# power_dist.net
KiCad netlist of a schematic drawn in EAGLE
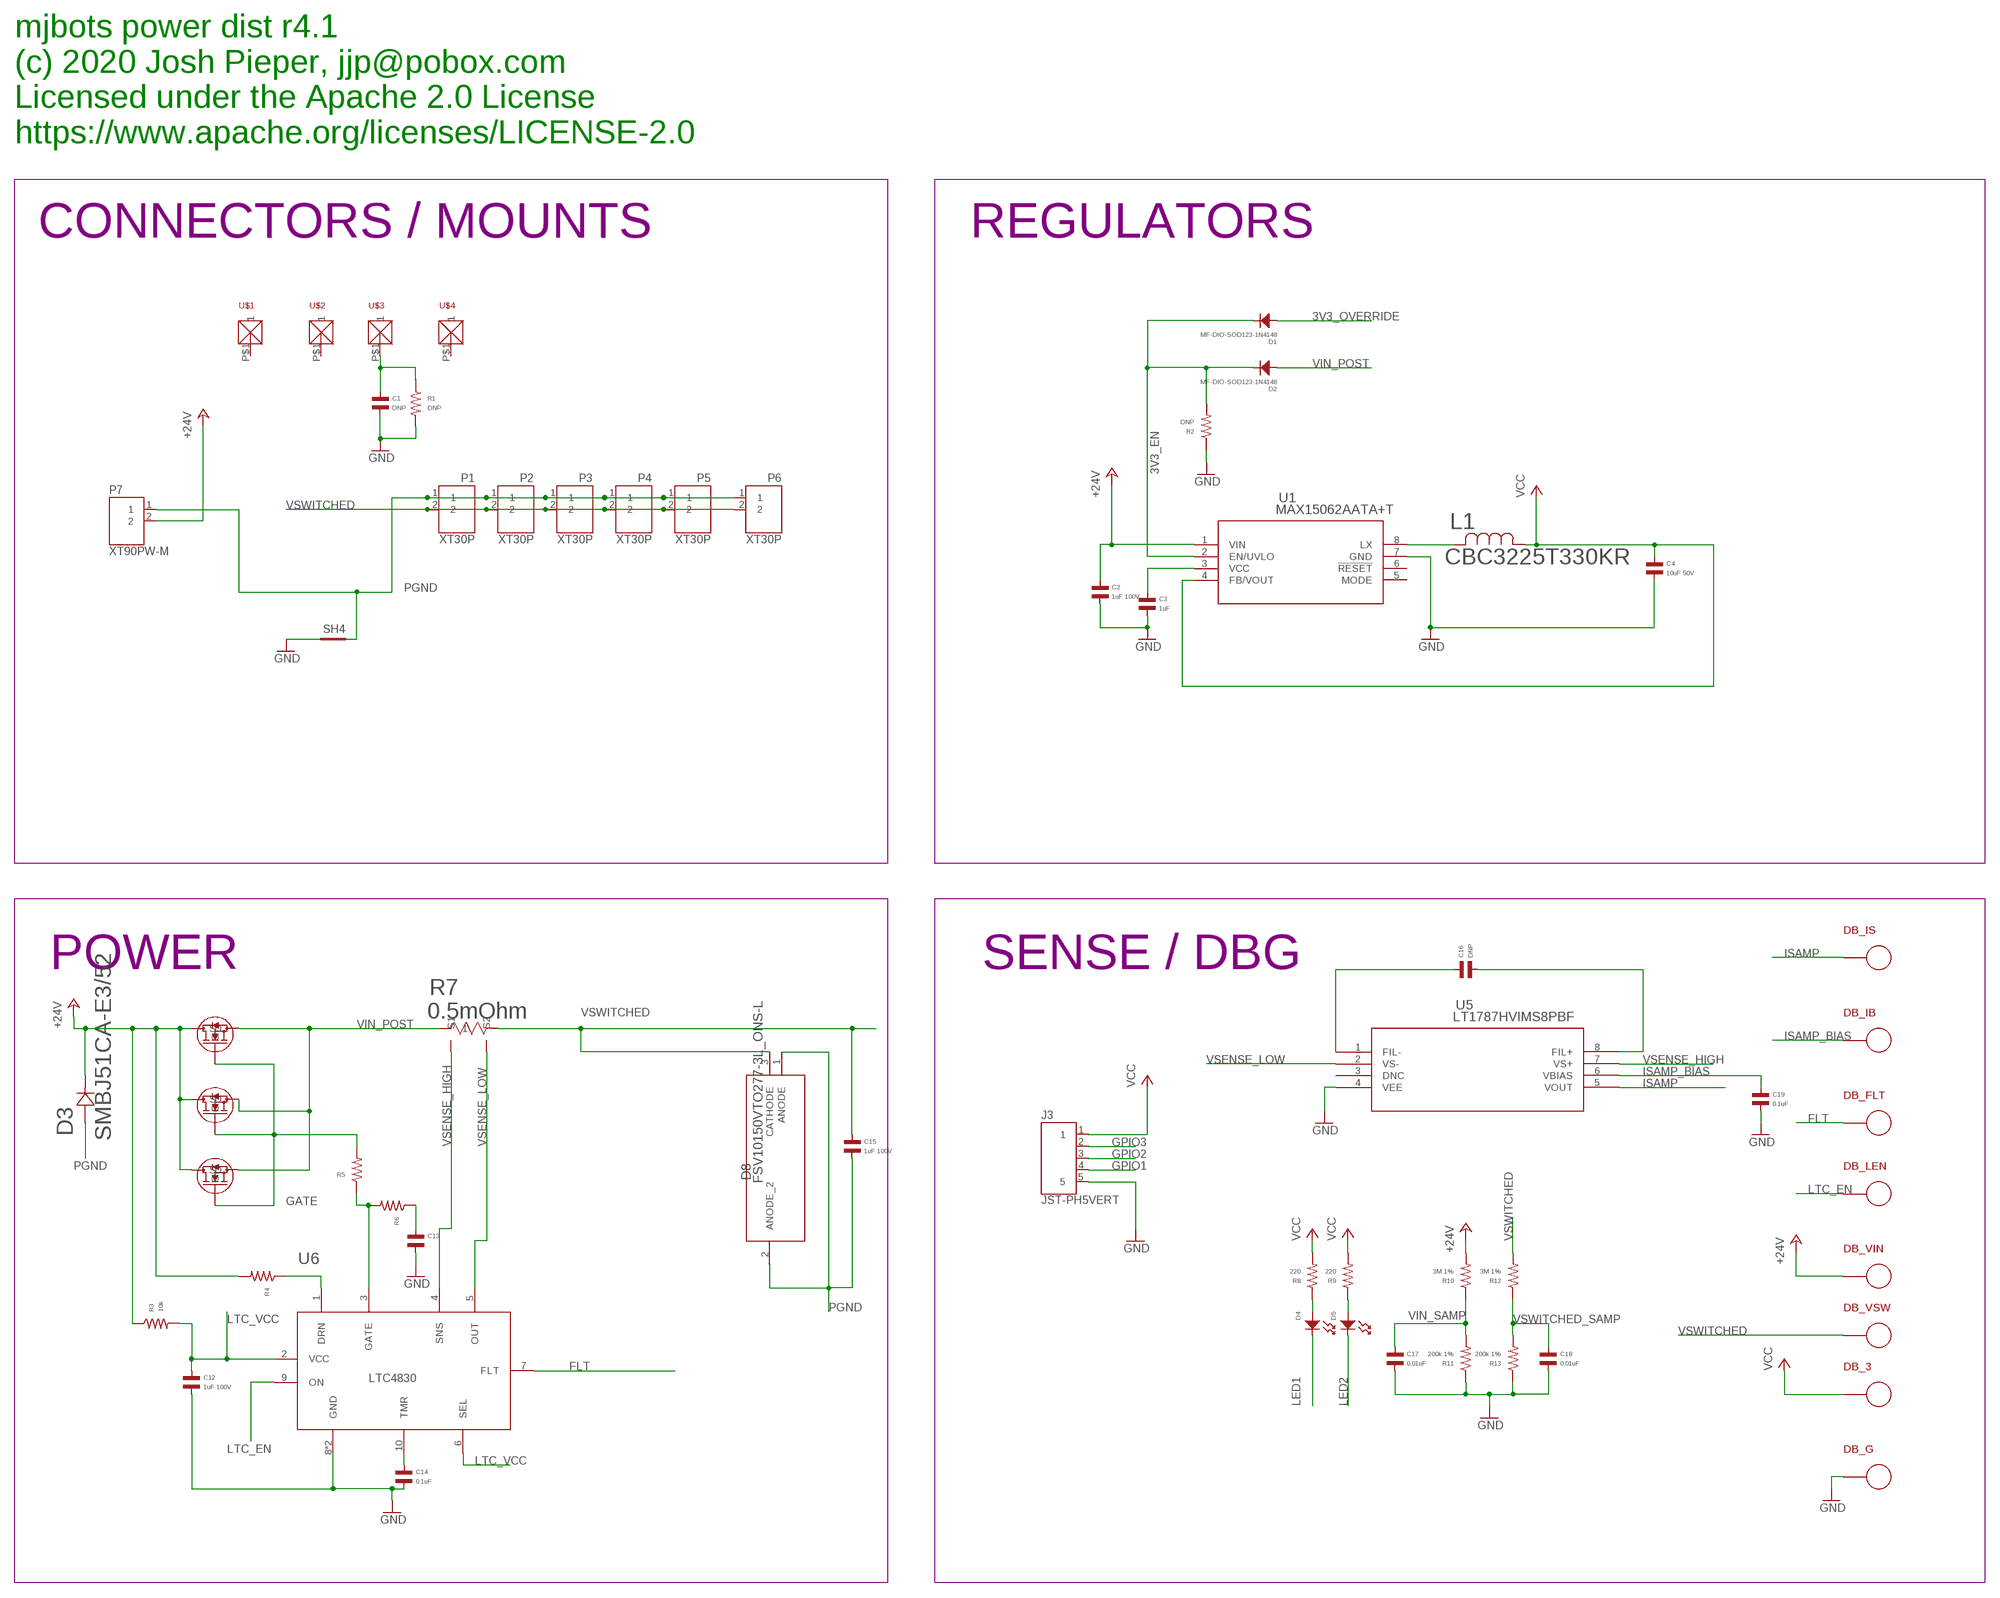
[diagram p0: schematic, sheet 1, part 1 of 2]
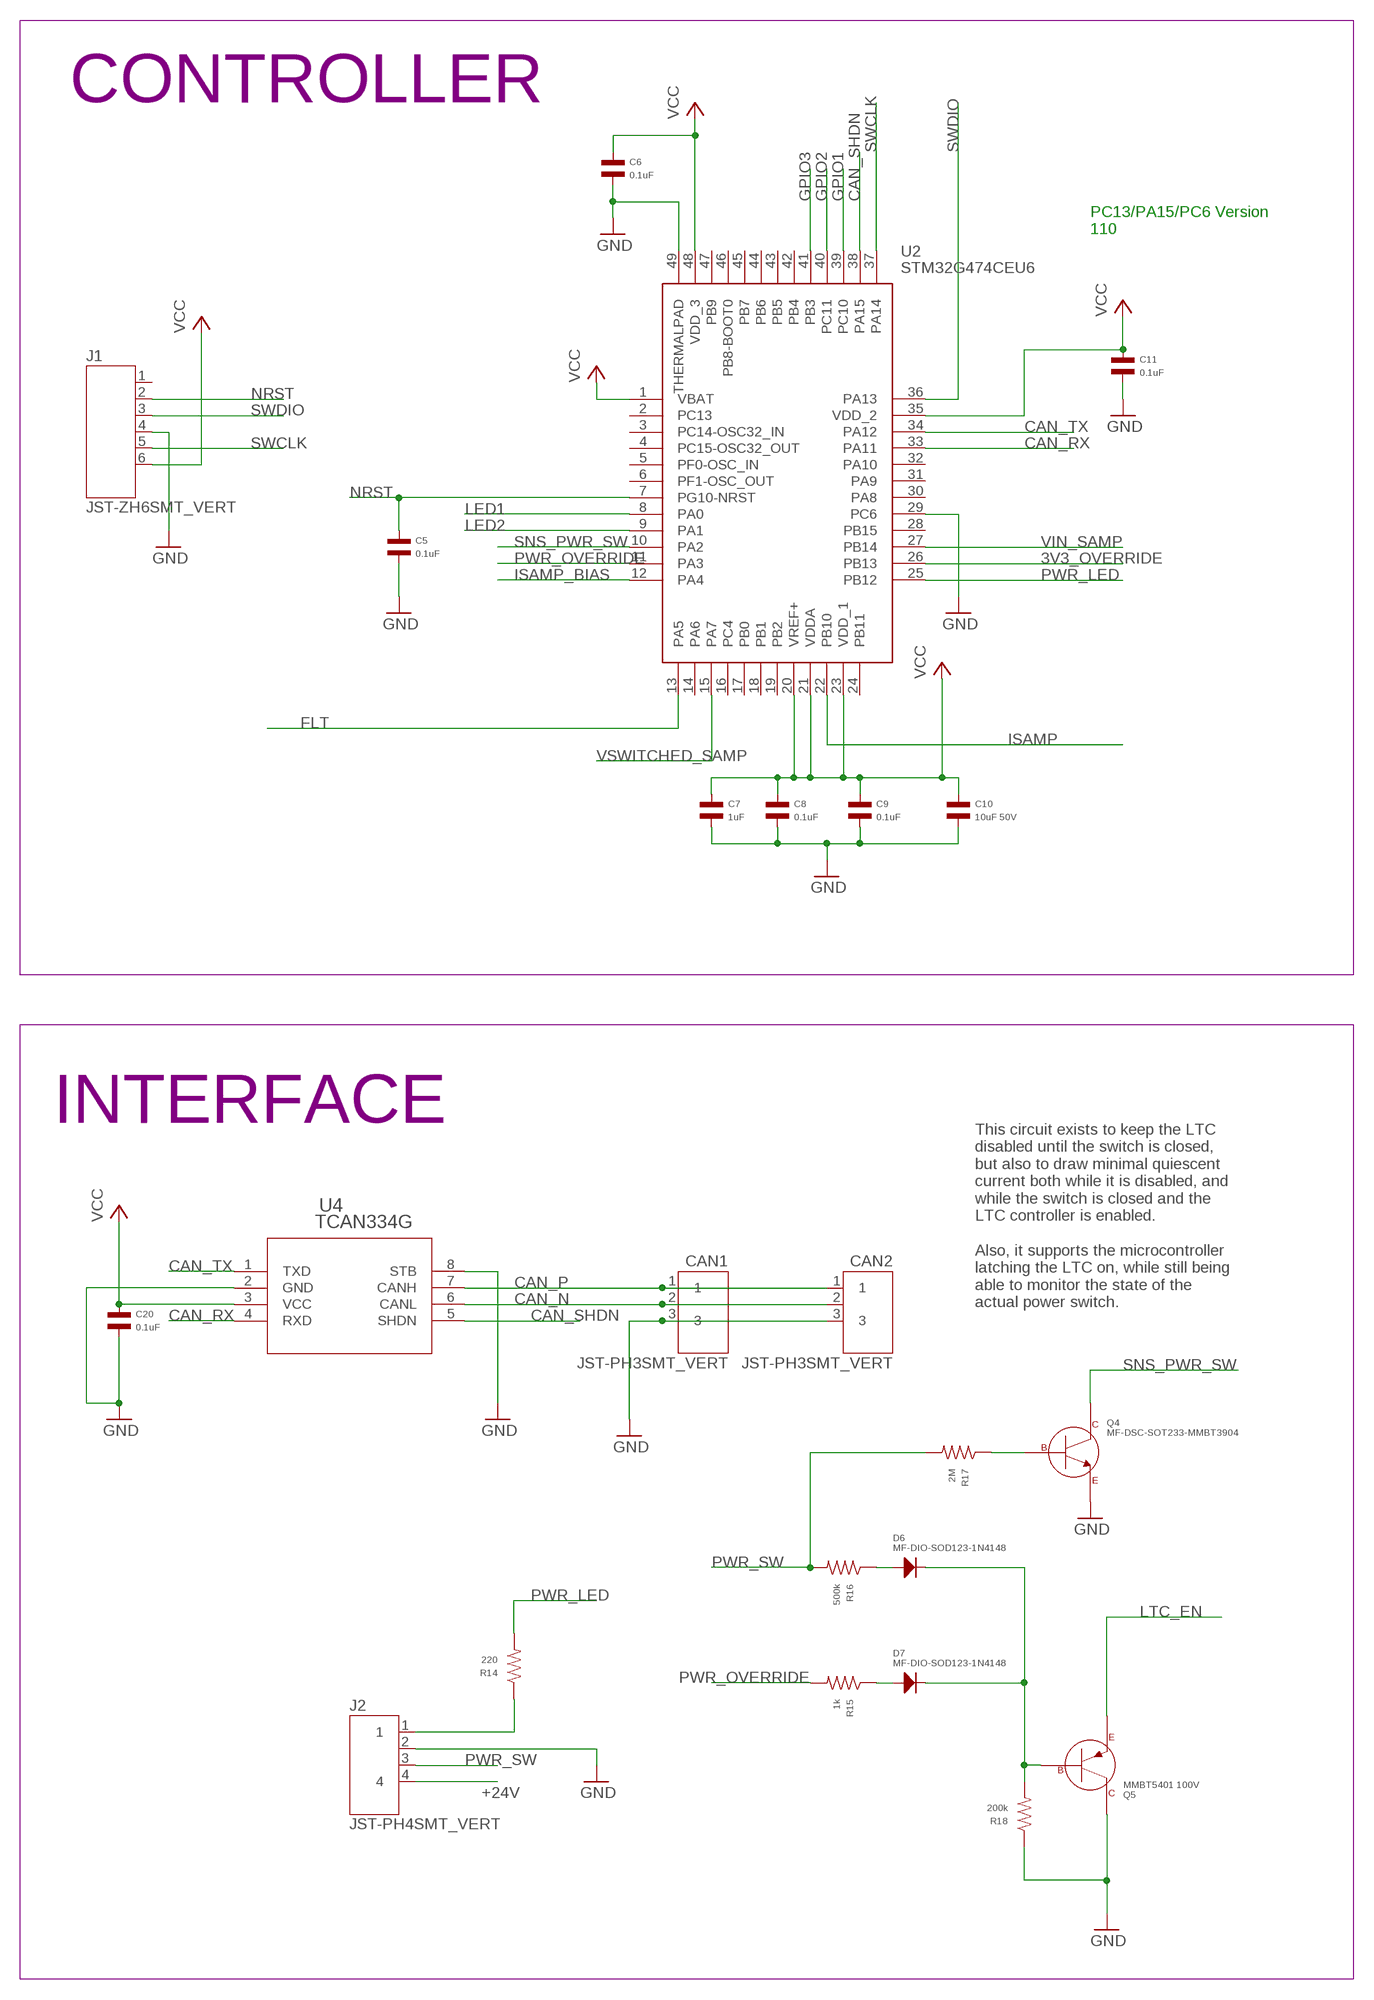
[diagram p1: schematic, sheet 1, part 2 of 2]

(export (version "E")
  (design (tool "Eeschema 10.0.6"))
  (components
    (comp (ref "C1")
      (value "DNP")
      (footprint "eagle-import:C0603")
      (fields (field (name "POPULATE") "0"))
      (libsource (lib "eagle-import") (part "CAPACITOR_NP_0603"))
    )
    (comp (ref "C2")
      (value "1uF 100V")
      (footprint "eagle-import:C0805")
      (fields (field (name "MF") "MURATA") (field (name "MPN") "GCM21BC72A105KE36L"))
      (libsource (lib "eagle-import") (part "CAPACITOR_NP_0805"))
    )
    (comp (ref "C3")
      (value "1uF")
      (footprint "eagle-import:C0603")
      (fields (field (name "HOUSEPART") "1") (field (name "MPN") "MF-CAP-0603-1uF"))
      (libsource (lib "eagle-import") (part "CAPACITOR_NP_0603"))
    )
    (comp (ref "C4")
      (value "10uF 50V")
      (footprint "eagle-import:C1206")
      (fields (field (name "MF") "TDK") (field (name "MPN") "C3216X7R1H106K160AE"))
      (libsource (lib "eagle-import") (part "CAPACITOR_NP_1206"))
    )
    (comp (ref "C5")
      (value "0.1uF")
      (footprint "eagle-import:C0603")
      (fields (field (name "HOUSEPART") "1") (field (name "MPN") "MF-CAP-0603-0.1uF"))
      (libsource (lib "eagle-import") (part "CAPACITOR_NP_0603"))
    )
    (comp (ref "C6")
      (value "0.1uF")
      (footprint "eagle-import:C0603")
      (fields (field (name "HOUSEPART") "1") (field (name "MPN") "MF-CAP-0603-0.1uF"))
      (libsource (lib "eagle-import") (part "CAPACITOR_NP_0603"))
    )
    (comp (ref "C7")
      (value "1uF")
      (footprint "eagle-import:C0603")
      (fields (field (name "HOUSEPART") "1") (field (name "MPN") "MF-CAP-0603-1uF"))
      (libsource (lib "eagle-import") (part "CAPACITOR_NP_0603"))
    )
    (comp (ref "C8")
      (value "0.1uF")
      (footprint "eagle-import:C0603")
      (fields (field (name "HOUSEPART") "1") (field (name "MPN") "MF-CAP-0603-0.1uF"))
      (libsource (lib "eagle-import") (part "CAPACITOR_NP_0603"))
    )
    (comp (ref "C9")
      (value "0.1uF")
      (footprint "eagle-import:C0603")
      (fields (field (name "HOUSEPART") "1") (field (name "MPN") "MF-CAP-0603-0.1uF"))
      (libsource (lib "eagle-import") (part "CAPACITOR_NP_0603"))
    )
    (comp (ref "C10")
      (value "10uF 50V")
      (footprint "eagle-import:C1206")
      (fields (field (name "MF") "TDK") (field (name "MPN") "C3216X7R1H106K160AE"))
      (libsource (lib "eagle-import") (part "CAPACITOR_NP_1206"))
    )
    (comp (ref "C11")
      (value "0.1uF")
      (footprint "eagle-import:C0603")
      (fields (field (name "HOUSEPART") "1") (field (name "MPN") "MF-CAP-0603-0.1uF"))
      (libsource (lib "eagle-import") (part "CAPACITOR_NP_0603"))
    )
    (comp (ref "C12")
      (value "1uF 100V")
      (footprint "eagle-import:C0805")
      (fields (field (name "MF") "MURATA") (field (name "MPN") "GCM21BC72A105KE36L"))
      (libsource (lib "eagle-import") (part "CAPACITOR_NP_0805"))
    )
    (comp (ref "C13")
      (value "CAPACITOR_NP_0603")
      (footprint "eagle-import:C0603")
      (fields (field (name "HOUSEPART") "1"))
      (libsource (lib "eagle-import") (part "CAPACITOR_NP_0603"))
    )
    (comp (ref "C14")
      (value "0.1uF")
      (footprint "eagle-import:C0603")
      (fields (field (name "HOUSEPART") "1") (field (name "MPN") "MF-CAP-0603-0.1uF"))
      (libsource (lib "eagle-import") (part "CAPACITOR_NP_0603"))
    )
    (comp (ref "C15")
      (value "1uF 100V")
      (footprint "eagle-import:C0805")
      (fields (field (name "MF") "MURATA") (field (name "MPN") "GCM21BC72A105KE36L"))
      (libsource (lib "eagle-import") (part "CAPACITOR_NP_0805"))
    )
    (comp (ref "C16")
      (value "DNP")
      (footprint "eagle-import:C0603")
      (fields (field (name "POPULATE") "0"))
      (libsource (lib "eagle-import") (part "CAPACITOR_NP_0603"))
    )
    (comp (ref "C17")
      (value "0.01uF")
      (footprint "eagle-import:C0603")
      (fields (field (name "HOUSEPART") "1") (field (name "MPN") "MF-CAP-0603-0.01uF"))
      (libsource (lib "eagle-import") (part "CAPACITOR_NP_0603"))
    )
    (comp (ref "C18")
      (value "0.01uF")
      (footprint "eagle-import:C0603")
      (fields (field (name "HOUSEPART") "1") (field (name "MPN") "MF-CAP-0603-0.01uF"))
      (libsource (lib "eagle-import") (part "CAPACITOR_NP_0603"))
    )
    (comp (ref "C19")
      (value "0.1uF")
      (footprint "eagle-import:C0603")
      (fields (field (name "HOUSEPART") "1") (field (name "MPN") "MF-CAP-0603-0.1uF"))
      (libsource (lib "eagle-import") (part "CAPACITOR_NP_0603"))
    )
    (comp (ref "C20")
      (value "0.1uF")
      (footprint "eagle-import:C0603")
      (fields (field (name "HOUSEPART") "1") (field (name "MPN") "MF-CAP-0603-0.1uF"))
      (libsource (lib "eagle-import") (part "CAPACITOR_NP_0603"))
    )
    (comp (ref "CAN1")
      (value "JST-PH3SMT_VERT")
      (footprint "eagle-import:JST_B3B_PH-SM4-TB(LF)(SN)")
      (fields (field (name "MF") "JST") (field (name "MPN") "B3B-PH-SM4-TB(LF)(SN)"))
      (libsource (lib "eagle-import") (part "JST-PH3SMT_VERT"))
    )
    (comp (ref "CAN2")
      (value "JST-PH3SMT_VERT")
      (footprint "eagle-import:JST_B3B_PH-SM4-TB(LF)(SN)")
      (fields (field (name "MF") "JST") (field (name "MPN") "B3B-PH-SM4-TB(LF)(SN)"))
      (libsource (lib "eagle-import") (part "JST-PH3SMT_VERT"))
    )
    (comp (ref "D1")
      (value "MF-DIO-SOD123-1N4148")
      (footprint "eagle-import:SOD-123")
      (fields (field (name "HOUSEPART") "YES"))
      (libsource (lib "eagle-import") (part "DIODES_SOD-123_1N4148"))
    )
    (comp (ref "D2")
      (value "MF-DIO-SOD123-1N4148")
      (footprint "eagle-import:SOD-123")
      (fields (field (name "HOUSEPART") "YES"))
      (libsource (lib "eagle-import") (part "DIODES_SOD-123_1N4148"))
    )
    (comp (ref "D3")
      (value "SMBJ51CA-E3/52")
      (footprint "eagle-import:DIODE_DO-214AC")
      (libsource (lib "eagle-import") (part "SMBJ51CA-E3/52"))
    )
    (comp (ref "D4")
      (value "LED_SINGLE-0603")
      (footprint "eagle-import:LED0603")
      (fields
        (field (name "HOUSEPART") "NO")
        (field (name "HOUSEPART_1") "1")
        (field (name "MPN") "MF-LED-0603-RED")
      )
      (libsource (lib "eagle-import") (part "LED_SINGLE-0603"))
    )
    (comp (ref "D5")
      (value "LED_SINGLE-0603")
      (footprint "eagle-import:LED0603")
      (fields
        (field (name "HOUSEPART") "NO")
        (field (name "HOUSEPART_1") "1")
        (field (name "MPN") "MF-LED-0603-RED")
      )
      (libsource (lib "eagle-import") (part "LED_SINGLE-0603"))
    )
    (comp (ref "D6")
      (value "MF-DIO-SOD123-1N4148")
      (footprint "eagle-import:SOD-123")
      (fields (field (name "HOUSEPART") "YES"))
      (libsource (lib "eagle-import") (part "DIODES_SOD-123_1N4148"))
    )
    (comp (ref "D7")
      (value "MF-DIO-SOD123-1N4148")
      (footprint "eagle-import:SOD-123")
      (fields (field (name "HOUSEPART") "YES"))
      (libsource (lib "eagle-import") (part "DIODES_SOD-123_1N4148"))
    )
    (comp (ref "D8")
      (value "FSV10150VTO277-3L_ONS-L")
      (footprint "eagle-import:TO277-3L_ONS-L")
      (fields
        (field (name "MANUFACTURER_PART_NUMBER") "FSV10150V")
        (field (name "COPYRIGHT") "Copyright (C) 2018 Accelerated Designs. All rights reserved")
      )
      (libsource (lib "eagle-import") (part "FSV10150VTO277-3L_ONS-L"))
    )
    (comp (ref "DB_3")
      (value "PAD24AWG_PAD")
      (footprint "eagle-import:24AWG_PAD")
      (libsource (lib "eagle-import") (part "PAD24AWG_PAD"))
    )
    (comp (ref "DB_FLT")
      (value "PAD24AWG_PAD")
      (footprint "eagle-import:24AWG_PAD")
      (libsource (lib "eagle-import") (part "PAD24AWG_PAD"))
    )
    (comp (ref "DB_G")
      (value "PAD24AWG_PAD")
      (footprint "eagle-import:24AWG_PAD")
      (libsource (lib "eagle-import") (part "PAD24AWG_PAD"))
    )
    (comp (ref "DB_IB")
      (value "PAD24AWG_PAD")
      (footprint "eagle-import:24AWG_PAD")
      (libsource (lib "eagle-import") (part "PAD24AWG_PAD"))
    )
    (comp (ref "DB_IS")
      (value "PAD24AWG_PAD")
      (footprint "eagle-import:24AWG_PAD")
      (libsource (lib "eagle-import") (part "PAD24AWG_PAD"))
    )
    (comp (ref "DB_LEN")
      (value "PAD24AWG_PAD")
      (footprint "eagle-import:24AWG_PAD")
      (libsource (lib "eagle-import") (part "PAD24AWG_PAD"))
    )
    (comp (ref "DB_VIN")
      (value "PAD24AWG_PAD")
      (footprint "eagle-import:24AWG_PAD")
      (libsource (lib "eagle-import") (part "PAD24AWG_PAD"))
    )
    (comp (ref "DB_VSW")
      (value "PAD24AWG_PAD")
      (footprint "eagle-import:24AWG_PAD")
      (libsource (lib "eagle-import") (part "PAD24AWG_PAD"))
    )
    (comp (ref "J1")
      (value "JST-ZH6SMT_VERT")
      (footprint "eagle-import:JST_B6B-ZR-SM4-TF(LF)(SN)")
      (fields (field (name "MF") "JST") (field (name "MPN") "B6B-ZR-SM4-TF(LF)(SN)"))
      (libsource (lib "eagle-import") (part "JST-ZH6SMT_VERT"))
    )
    (comp (ref "J2")
      (value "JST-PH4SMT_VERT")
      (footprint "eagle-import:JST_B4B_PH-SM4-TB(LF)(SN)")
      (fields (field (name "MF") "JST") (field (name "MPN") "B4B-PH-SM4-TB(LF)(SN)"))
      (libsource (lib "eagle-import") (part "JST-PH4SMT_VERT"))
    )
    (comp (ref "J3")
      (value "JST-PH5VERT")
      (footprint "eagle-import:JST_B5B_PH-SM4-TB(LF)(SN)")
      (fields (field (name "MF") "JST") (field (name "MPN") "B5B-PH-SM4-TB(LF)(SN)"))
      (libsource (lib "eagle-import") (part "JST-PH5VERT"))
    )
    (comp (ref "L1")
      (value "CBC3225T330KR")
      (footprint "eagle-import:IND_TAIYO_CBC3225_TAY")
      (libsource (lib "eagle-import") (part "CBC3225T330KR"))
    )
    (comp (ref "P1")
      (value "XT30P")
      (footprint "eagle-import:XT30P")
      (fields (field (name "MF") "AMASS") (field (name "MPN") "XT30UPB-F"))
      (libsource (lib "eagle-import") (part "XT30P"))
    )
    (comp (ref "P2")
      (value "XT30P")
      (footprint "eagle-import:XT30P")
      (fields (field (name "MF") "AMASS") (field (name "MPN") "XT30UPB-F"))
      (libsource (lib "eagle-import") (part "XT30P"))
    )
    (comp (ref "P3")
      (value "XT30P")
      (footprint "eagle-import:XT30P")
      (fields (field (name "MF") "AMASS") (field (name "MPN") "XT30UPB-F"))
      (libsource (lib "eagle-import") (part "XT30P"))
    )
    (comp (ref "P4")
      (value "XT30P")
      (footprint "eagle-import:XT30P")
      (fields (field (name "MF") "AMASS") (field (name "MPN") "XT30UPB-F"))
      (libsource (lib "eagle-import") (part "XT30P"))
    )
    (comp (ref "P5")
      (value "XT30P")
      (footprint "eagle-import:XT30P")
      (fields (field (name "MF") "AMASS") (field (name "MPN") "XT30UPB-F"))
      (libsource (lib "eagle-import") (part "XT30P"))
    )
    (comp (ref "P6")
      (value "XT30P")
      (footprint "eagle-import:XT30P")
      (fields (field (name "MF") "AMASS") (field (name "MPN") "XT30UPB-F"))
      (libsource (lib "eagle-import") (part "XT30P"))
    )
    (comp (ref "P7")
      (value "XT90PW-M")
      (footprint "eagle-import:XT90PW-M")
      (libsource (lib "eagle-import") (part "XT90PW-M"))
    )
    (comp (ref "Q1")
      (value "PSMN4R8-100BSEJ")
      (footprint "eagle-import:D2PAK_SOT404_NEX")
      (fields (field (name "COPYRIGHT") "Copyright (C) 2018 Accelerated Designs. All rights reserved"))
      (libsource (lib "eagle-import") (part "PSMN4R8-100BSEJ"))
    )
    (comp (ref "Q2")
      (value "PSMN4R8-100BSEJ")
      (footprint "eagle-import:D2PAK_SOT404_NEX")
      (fields (field (name "COPYRIGHT") "Copyright (C) 2018 Accelerated Designs. All rights reserved"))
      (libsource (lib "eagle-import") (part "PSMN4R8-100BSEJ"))
    )
    (comp (ref "Q3")
      (value "PSMN4R8-100BSEJ")
      (footprint "eagle-import:D2PAK_SOT404_NEX")
      (fields (field (name "COPYRIGHT") "Copyright (C) 2018 Accelerated Designs. All rights reserved"))
      (libsource (lib "eagle-import") (part "PSMN4R8-100BSEJ"))
    )
    (comp (ref "Q4")
      (value "MF-DSC-SOT233-MMBT3904")
      (footprint "eagle-import:SOT-23-3")
      (fields (field (name "HOUSEPART") "YES"))
      (libsource (lib "eagle-import") (part "NPN_BJT_SOT-23-3MMBT3904"))
    )
    (comp (ref "Q5")
      (value "MMBT5401 100V")
      (footprint "eagle-import:SOT-23-3")
      (fields
        (field (name "HOUSEPART") "YES")
        (field (name "MPN") "MF-DSC-SOT233-MMBT3906")
        (field (name "MF") "DIODES")
        (field (name "MPN_1") "MMBT5401-7-F")
      )
      (libsource (lib "eagle-import") (part "PNP_BJT_SOT-23-3_MMBT3906"))
    )
    (comp (ref "R1")
      (value "DNP")
      (footprint "eagle-import:R0603")
      (fields (field (name "POPULATE") "0"))
      (libsource (lib "eagle-import") (part "RESISTOR_0603"))
    )
    (comp (ref "R2")
      (value "DNP")
      (footprint "eagle-import:R0603")
      (fields (field (name "HOUSEPART") "1"))
      (libsource (lib "eagle-import") (part "RESISTOR_0603"))
    )
    (comp (ref "R3")
      (value "10k")
      (footprint "eagle-import:R0603")
      (fields (field (name "HOUSEPART") "1"))
      (libsource (lib "eagle-import") (part "RESISTOR_0603"))
    )
    (comp (ref "R4")
      (value "RESISTOR_0603")
      (footprint "eagle-import:R0603")
      (fields (field (name "HOUSEPART") "1"))
      (libsource (lib "eagle-import") (part "RESISTOR_0603"))
    )
    (comp (ref "R5")
      (value "RESISTOR_0603")
      (footprint "eagle-import:R0603")
      (fields (field (name "HOUSEPART") "1"))
      (libsource (lib "eagle-import") (part "RESISTOR_0603"))
    )
    (comp (ref "R6")
      (value "RESISTOR_0603")
      (footprint "eagle-import:R0603")
      (fields (field (name "HOUSEPART") "1"))
      (libsource (lib "eagle-import") (part "RESISTOR_0603"))
    )
    (comp (ref "R7")
      (value "0.5mOhm")
      (footprint "eagle-import:SHUNT2512")
      (fields (field (name "MF") "VISHAY DALE") (field (name "MPN") "WSLF2512L5000FEA"))
      (libsource (lib "eagle-import") (part "SENSE_RESISTOR2512"))
    )
    (comp (ref "R8")
      (value "220")
      (footprint "eagle-import:R0603")
      (fields (field (name "HOUSEPART") "1") (field (name "MPN") "MF-RES-0603-220"))
      (libsource (lib "eagle-import") (part "RESISTOR_0603"))
    )
    (comp (ref "R9")
      (value "220")
      (footprint "eagle-import:R0603")
      (fields (field (name "HOUSEPART") "1") (field (name "MPN") "MF-RES-0603-220"))
      (libsource (lib "eagle-import") (part "RESISTOR_0603"))
    )
    (comp (ref "R10")
      (value "3M 1%")
      (footprint "eagle-import:R0603")
      (fields (field (name "HOUSEPART") "1"))
      (libsource (lib "eagle-import") (part "RESISTOR_0603"))
    )
    (comp (ref "R11")
      (value "200k 1%")
      (footprint "eagle-import:R0603")
      (fields (field (name "HOUSEPART") "1"))
      (libsource (lib "eagle-import") (part "RESISTOR_0603"))
    )
    (comp (ref "R12")
      (value "3M 1%")
      (footprint "eagle-import:R0603")
      (fields (field (name "HOUSEPART") "1"))
      (libsource (lib "eagle-import") (part "RESISTOR_0603"))
    )
    (comp (ref "R13")
      (value "200k 1%")
      (footprint "eagle-import:R0603")
      (fields (field (name "HOUSEPART") "1"))
      (libsource (lib "eagle-import") (part "RESISTOR_0603"))
    )
    (comp (ref "R14")
      (value "220")
      (footprint "eagle-import:R0603")
      (fields (field (name "HOUSEPART") "1") (field (name "MPN") "MF-RES-0603-220"))
      (libsource (lib "eagle-import") (part "RESISTOR_0603"))
    )
    (comp (ref "R15")
      (value "1k")
      (footprint "eagle-import:R0603")
      (fields (field (name "HOUSEPART") "1"))
      (libsource (lib "eagle-import") (part "RESISTOR_0603"))
    )
    (comp (ref "R16")
      (value "500k")
      (footprint "eagle-import:R0603")
      (fields (field (name "HOUSEPART") "1"))
      (libsource (lib "eagle-import") (part "RESISTOR_0603"))
    )
    (comp (ref "R17")
      (value "2M")
      (footprint "eagle-import:R0603")
      (fields (field (name "HOUSEPART") "1"))
      (libsource (lib "eagle-import") (part "RESISTOR_0603"))
    )
    (comp (ref "R18")
      (value "200k")
      (footprint "eagle-import:R0603")
      (fields (field (name "HOUSEPART") "1"))
      (libsource (lib "eagle-import") (part "RESISTOR_0603"))
    )
    (comp (ref "SH4")
      (value "SHORTBIG")
      (footprint "eagle-import:SHORT_TOP-BIG")
      (libsource (lib "eagle-import") (part "SHORTBIG"))
    )
    (comp (ref "U$1")
      (value "MOUNT")
      (footprint "eagle-import:M2.5MOUNT")
      (libsource (lib "eagle-import") (part "MOUNT"))
    )
    (comp (ref "U$2")
      (value "MOUNT")
      (footprint "eagle-import:M2.5MOUNT")
      (libsource (lib "eagle-import") (part "MOUNT"))
    )
    (comp (ref "U$3")
      (value "MOUNT")
      (footprint "eagle-import:M2.5MOUNT")
      (libsource (lib "eagle-import") (part "MOUNT"))
    )
    (comp (ref "U$4")
      (value "MOUNT")
      (footprint "eagle-import:M2.5MOUNT")
      (libsource (lib "eagle-import") (part "MOUNT"))
    )
    (comp (ref "U1")
      (value "MAX15062AATA+T")
      (footprint "eagle-import:21-0487A_MXM")
      (fields (field (name "COPYRIGHT") "Copyright (C) 2018 Accelerated Designs. All rights reserved"))
      (libsource (lib "eagle-import") (part "MAX15062AATA+T"))
    )
    (comp (ref "U2")
      (value "STM32G474CEU6")
      (footprint "eagle-import:QFN50P700X700X60-49N")
      (fields (field (name "MOUSER_PART_NUMBER") "511-STM32G474CEU6") (field (name "MF") "ST"))
      (libsource (lib "eagle-import") (part "STM32G474CEU6"))
    )
    (comp (ref "U4")
      (value "TCAN334G")
      (footprint "eagle-import:SOIC8")
      (fields (field (name "MF") "TI") (field (name "MPN") "TCAN334GDR"))
      (libsource (lib "eagle-import") (part "TCAN334G"))
    )
    (comp (ref "U5")
      (value "LT1787HVIMS8PBF")
      (footprint "eagle-import:MSOP-8_MS")
      (fields
        (field (name "DIGI-KEY_PART_NUMBER") "LT1787HVIMS8#PBF-ND")
        (field (name "MF") "Linear Technology")
        (field (name "MP") "LT1787HVIMS8#PBF")
      )
      (libsource (lib "eagle-import") (part "LT1787HVIMS8PBF"))
    )
    (comp (ref "U6")
      (value "LTC4830")
      (footprint "eagle-import:DFN10")
      (libsource (lib "eagle-import") (part "LTC4830"))
    )
  )
  (nets
    (net (code "1") (name "+24V") (class "Default")
      (node (ref "C2") (pin "P$1") (pinfunction "P$1_P$1") (pintype "passive"))
      (node (ref "D3") (pin "1") (pinfunction "1_1") (pintype "passive"))
      (node (ref "DB_VIN") (pin "P$1") (pinfunction "P$1_P$1") (pintype "bidirectional"))
      (node (ref "J2") (pin "4") (pinfunction "4_4") (pintype "passive"))
      (node (ref "P7") (pin "2") (pinfunction "2_2") (pintype "passive"))
      (node (ref "Q1") (pin "2") (pinfunction "D_2") (pintype "passive"))
      (node (ref "Q2") (pin "2") (pinfunction "D_2") (pintype "passive"))
      (node (ref "Q3") (pin "2") (pinfunction "D_2") (pintype "passive"))
      (node (ref "R10") (pin "P$2") (pinfunction "P$2_P$2") (pintype "passive"))
      (node (ref "R3") (pin "P$1") (pinfunction "P$1_P$1") (pintype "passive"))
      (node (ref "R4") (pin "P$2") (pinfunction "P$2_P$2") (pintype "passive"))
      (node (ref "U1") (pin "1") (pinfunction "VIN_1") (pintype "input"))
    )
    (net (code "2") (name "/3V3_EN") (class "Default")
      (node (ref "D1") (pin "CATHODE") (pinfunction "CATHODE_CATHODE") (pintype "bidirectional"))
      (node (ref "D2") (pin "CATHODE") (pinfunction "CATHODE_CATHODE") (pintype "bidirectional"))
      (node (ref "R2") (pin "P$2") (pinfunction "P$2_P$2") (pintype "passive"))
      (node (ref "U1") (pin "2") (pinfunction "EN/UVLO_2") (pintype "input"))
    )
    (net (code "3") (name "/3V3_OVERRIDE") (class "Default")
      (node (ref "D1") (pin "ANODE") (pinfunction "ANODE_ANODE") (pintype "bidirectional"))
      (node (ref "U2") (pin "26") (pinfunction "PB13_26") (pintype "bidirectional"))
    )
    (net (code "4") (name "/CAN_N") (class "Default")
      (node (ref "CAN1") (pin "2") (pinfunction "2_2") (pintype "passive"))
      (node (ref "CAN2") (pin "2") (pinfunction "2_2") (pintype "passive"))
      (node (ref "U4") (pin "6") (pinfunction "CANL_6") (pintype "bidirectional"))
    )
    (net (code "5") (name "/CAN_P") (class "Default")
      (node (ref "CAN1") (pin "1") (pinfunction "1_1") (pintype "passive"))
      (node (ref "CAN2") (pin "1") (pinfunction "1_1") (pintype "passive"))
      (node (ref "U4") (pin "7") (pinfunction "CANH_7") (pintype "bidirectional"))
    )
    (net (code "6") (name "/CAN_RX") (class "Default")
      (node (ref "U2") (pin "33") (pinfunction "PA11_33") (pintype "bidirectional"))
      (node (ref "U4") (pin "4") (pinfunction "RXD_4") (pintype "output"))
    )
    (net (code "7") (name "/CAN_SHDN") (class "Default")
      (node (ref "U2") (pin "38") (pinfunction "PA15_38") (pintype "bidirectional"))
      (node (ref "U4") (pin "5") (pinfunction "SHDN_5") (pintype "input"))
    )
    (net (code "8") (name "/CAN_TX") (class "Default")
      (node (ref "U2") (pin "34") (pinfunction "PA12_34") (pintype "bidirectional"))
      (node (ref "U4") (pin "1") (pinfunction "TXD_1") (pintype "input"))
    )
    (net (code "9") (name "/FLT") (class "Default")
      (node (ref "DB_FLT") (pin "P$1") (pinfunction "P$1_P$1") (pintype "bidirectional"))
      (node (ref "U2") (pin "13") (pinfunction "PA5_13") (pintype "bidirectional"))
      (node (ref "U6") (pin "7") (pinfunction "FLT_7") (pintype "bidirectional"))
    )
    (net (code "10") (name "/GATE") (class "Default")
      (node (ref "Q1") (pin "1") (pinfunction "G_1") (pintype "passive"))
      (node (ref "Q2") (pin "1") (pinfunction "G_1") (pintype "passive"))
      (node (ref "Q3") (pin "1") (pinfunction "G_1") (pintype "passive"))
      (node (ref "R5") (pin "P$2") (pinfunction "P$2_P$2") (pintype "passive"))
    )
    (net (code "11") (name "/GPIO1") (class "Default")
      (node (ref "J3") (pin "4") (pinfunction "4_4") (pintype "passive"))
      (node (ref "U2") (pin "39") (pinfunction "PC10_39") (pintype "bidirectional"))
    )
    (net (code "12") (name "/GPIO2") (class "Default")
      (node (ref "J3") (pin "3") (pinfunction "3_3") (pintype "passive"))
      (node (ref "U2") (pin "40") (pinfunction "PC11_40") (pintype "bidirectional"))
    )
    (net (code "13") (name "/GPIO3") (class "Default")
      (node (ref "J3") (pin "2") (pinfunction "2_2") (pintype "passive"))
      (node (ref "U2") (pin "41") (pinfunction "PB3_41") (pintype "bidirectional"))
    )
    (net (code "14") (name "/ISAMP") (class "Default")
      (node (ref "DB_IS") (pin "P$1") (pinfunction "P$1_P$1") (pintype "bidirectional"))
      (node (ref "U2") (pin "22") (pinfunction "PB10_22") (pintype "bidirectional"))
      (node (ref "U5") (pin "5") (pinfunction "VOUT_5") (pintype "output"))
    )
    (net (code "15") (name "/ISAMP_BIAS") (class "Default")
      (node (ref "C19") (pin "P$1") (pinfunction "P$1_P$1") (pintype "passive"))
      (node (ref "DB_IB") (pin "P$1") (pinfunction "P$1_P$1") (pintype "bidirectional"))
      (node (ref "U2") (pin "12") (pinfunction "PA4_12") (pintype "bidirectional"))
      (node (ref "U5") (pin "6") (pinfunction "VBIAS_6") (pintype "output"))
    )
    (net (code "16") (name "/LED1") (class "Default")
      (node (ref "D4") (pin "CATHODE") (pinfunction "CATHODE_CATHODE") (pintype "power_in"))
      (node (ref "U2") (pin "8") (pinfunction "PA0_8") (pintype "bidirectional"))
    )
    (net (code "17") (name "/LED2") (class "Default")
      (node (ref "D5") (pin "CATHODE") (pinfunction "CATHODE_CATHODE") (pintype "power_in"))
      (node (ref "U2") (pin "9") (pinfunction "PA1_9") (pintype "bidirectional"))
    )
    (net (code "18") (name "/LTC_EN") (class "Default")
      (node (ref "DB_LEN") (pin "P$1") (pinfunction "P$1_P$1") (pintype "bidirectional"))
      (node (ref "Q5") (pin "P$2") (pinfunction "EMITTER_P$2") (pintype "bidirectional"))
      (node (ref "U6") (pin "9") (pinfunction "ON_9") (pintype "bidirectional"))
    )
    (net (code "19") (name "/LTC_VCC") (class "Default")
      (node (ref "C12") (pin "P$1") (pinfunction "P$1_P$1") (pintype "passive"))
      (node (ref "R3") (pin "P$2") (pinfunction "P$2_P$2") (pintype "passive"))
      (node (ref "U6") (pin "2") (pinfunction "VCC_2") (pintype "bidirectional"))
      (node (ref "U6") (pin "6") (pinfunction "SEL_6") (pintype "bidirectional"))
    )
    (net (code "20") (name "/NRST") (class "Default")
      (node (ref "C5") (pin "P$1") (pinfunction "P$1_P$1") (pintype "passive"))
      (node (ref "J1") (pin "2") (pinfunction "2_2") (pintype "passive"))
      (node (ref "U2") (pin "7") (pinfunction "PG10-NRST_7") (pintype "bidirectional"))
    )
    (net (code "21") (name "/PGND") (class "Default")
      (node (ref "C15") (pin "P$2") (pinfunction "P$2_P$2") (pintype "passive"))
      (node (ref "D3") (pin "2") (pinfunction "2_2") (pintype "passive"))
      (node (ref "D8") (pin "1") (pinfunction "ANODE_1") (pintype "passive"))
      (node (ref "D8") (pin "2") (pinfunction "ANODE_2_2") (pintype "passive"))
      (node (ref "P1") (pin "1") (pinfunction "1_1") (pintype "passive"))
      (node (ref "P2") (pin "1") (pinfunction "1_1") (pintype "passive"))
      (node (ref "P3") (pin "1") (pinfunction "1_1") (pintype "passive"))
      (node (ref "P4") (pin "1") (pinfunction "1_1") (pintype "passive"))
      (node (ref "P5") (pin "1") (pinfunction "1_1") (pintype "passive"))
      (node (ref "P6") (pin "1") (pinfunction "1_1") (pintype "passive"))
      (node (ref "P7") (pin "1") (pinfunction "1_1") (pintype "passive"))
      (node (ref "SH4") (pin "2") (pinfunction "P$2_2") (pintype "bidirectional"))
    )
    (net (code "22") (name "/PWR_LED") (class "Default")
      (node (ref "R14") (pin "P$2") (pinfunction "P$2_P$2") (pintype "passive"))
      (node (ref "U2") (pin "25") (pinfunction "PB12_25") (pintype "bidirectional"))
    )
    (net (code "23") (name "/PWR_OVERRIDE") (class "Default")
      (node (ref "R15") (pin "P$2") (pinfunction "P$2_P$2") (pintype "passive"))
      (node (ref "U2") (pin "11") (pinfunction "PA3_11") (pintype "bidirectional"))
    )
    (net (code "24") (name "/PWR_SW") (class "Default")
      (node (ref "J2") (pin "3") (pinfunction "3_3") (pintype "passive"))
      (node (ref "R16") (pin "P$2") (pinfunction "P$2_P$2") (pintype "passive"))
      (node (ref "R17") (pin "P$2") (pinfunction "P$2_P$2") (pintype "passive"))
    )
    (net (code "25") (name "/SNS_PWR_SW") (class "Default")
      (node (ref "Q4") (pin "P$3") (pinfunction "COLLECTOR_P$3") (pintype "bidirectional"))
      (node (ref "U2") (pin "10") (pinfunction "PA2_10") (pintype "bidirectional"))
    )
    (net (code "26") (name "/SWCLK") (class "Default")
      (node (ref "J1") (pin "5") (pinfunction "5_5") (pintype "passive"))
      (node (ref "U2") (pin "37") (pinfunction "PA14_37") (pintype "bidirectional"))
    )
    (net (code "27") (name "/SWDIO") (class "Default")
      (node (ref "J1") (pin "3") (pinfunction "3_3") (pintype "passive"))
      (node (ref "U2") (pin "36") (pinfunction "PA13_36") (pintype "bidirectional"))
    )
    (net (code "28") (name "/VIN_POST") (class "Default")
      (node (ref "D2") (pin "ANODE") (pinfunction "ANODE_ANODE") (pintype "bidirectional"))
      (node (ref "Q1") (pin "3") (pinfunction "S_3") (pintype "passive"))
      (node (ref "Q2") (pin "3") (pinfunction "S_3") (pintype "passive"))
      (node (ref "Q3") (pin "3") (pinfunction "S_3") (pintype "passive"))
      (node (ref "R7") (pin "1") (pinfunction "1_1") (pintype "passive"))
    )
    (net (code "29") (name "/VIN_SAMP") (class "Default")
      (node (ref "C17") (pin "P$1") (pinfunction "P$1_P$1") (pintype "passive"))
      (node (ref "R10") (pin "P$1") (pinfunction "P$1_P$1") (pintype "passive"))
      (node (ref "R11") (pin "P$2") (pinfunction "P$2_P$2") (pintype "passive"))
      (node (ref "U2") (pin "27") (pinfunction "PB14_27") (pintype "bidirectional"))
    )
    (net (code "30") (name "/VSENSE_HIGH") (class "Default")
      (node (ref "R7") (pin "3") (pinfunction "S1_3") (pintype "passive"))
      (node (ref "U5") (pin "7") (pinfunction "VS+_7") (pintype "input"))
      (node (ref "U6") (pin "4") (pinfunction "SNS_4") (pintype "bidirectional"))
    )
    (net (code "31") (name "/VSENSE_LOW") (class "Default")
      (node (ref "R7") (pin "4") (pinfunction "S2_4") (pintype "passive"))
      (node (ref "U5") (pin "2") (pinfunction "VS-_2") (pintype "input"))
      (node (ref "U6") (pin "5") (pinfunction "OUT_5") (pintype "bidirectional"))
    )
    (net (code "32") (name "/VSWITCHED") (class "Default")
      (node (ref "C15") (pin "P$1") (pinfunction "P$1_P$1") (pintype "passive"))
      (node (ref "D8") (pin "3") (pinfunction "CATHODE_3") (pintype "passive"))
      (node (ref "DB_VSW") (pin "P$1") (pinfunction "P$1_P$1") (pintype "bidirectional"))
      (node (ref "P1") (pin "2") (pinfunction "2_2") (pintype "passive"))
      (node (ref "P2") (pin "2") (pinfunction "2_2") (pintype "passive"))
      (node (ref "P3") (pin "2") (pinfunction "2_2") (pintype "passive"))
      (node (ref "P4") (pin "2") (pinfunction "2_2") (pintype "passive"))
      (node (ref "P5") (pin "2") (pinfunction "2_2") (pintype "passive"))
      (node (ref "P6") (pin "2") (pinfunction "2_2") (pintype "passive"))
      (node (ref "R12") (pin "P$2") (pinfunction "P$2_P$2") (pintype "passive"))
      (node (ref "R7") (pin "2") (pinfunction "2_2") (pintype "passive"))
    )
    (net (code "33") (name "/VSWITCHED_SAMP") (class "Default")
      (node (ref "C18") (pin "P$1") (pinfunction "P$1_P$1") (pintype "passive"))
      (node (ref "R12") (pin "P$1") (pinfunction "P$1_P$1") (pintype "passive"))
      (node (ref "R13") (pin "P$2") (pinfunction "P$2_P$2") (pintype "passive"))
      (node (ref "U2") (pin "15") (pinfunction "PA7_15") (pintype "bidirectional"))
    )
    (net (code "34") (name "GND") (class "Default")
      (node (ref "C1") (pin "P$2") (pinfunction "P$2_P$2") (pintype "passive"))
      (node (ref "C10") (pin "P$2") (pinfunction "P$2_P$2") (pintype "passive"))
      (node (ref "C11") (pin "P$2") (pinfunction "P$2_P$2") (pintype "passive"))
      (node (ref "C12") (pin "P$2") (pinfunction "P$2_P$2") (pintype "passive"))
      (node (ref "C13") (pin "P$2") (pinfunction "P$2_P$2") (pintype "passive"))
      (node (ref "C14") (pin "P$2") (pinfunction "P$2_P$2") (pintype "passive"))
      (node (ref "C17") (pin "P$2") (pinfunction "P$2_P$2") (pintype "passive"))
      (node (ref "C18") (pin "P$2") (pinfunction "P$2_P$2") (pintype "passive"))
      (node (ref "C19") (pin "P$2") (pinfunction "P$2_P$2") (pintype "passive"))
      (node (ref "C2") (pin "P$2") (pinfunction "P$2_P$2") (pintype "passive"))
      (node (ref "C20") (pin "P$2") (pinfunction "P$2_P$2") (pintype "passive"))
      (node (ref "C3") (pin "P$2") (pinfunction "P$2_P$2") (pintype "passive"))
      (node (ref "C4") (pin "P$2") (pinfunction "P$2_P$2") (pintype "passive"))
      (node (ref "C5") (pin "P$2") (pinfunction "P$2_P$2") (pintype "passive"))
      (node (ref "C6") (pin "P$2") (pinfunction "P$2_P$2") (pintype "passive"))
      (node (ref "C7") (pin "P$2") (pinfunction "P$2_P$2") (pintype "passive"))
      (node (ref "C8") (pin "P$2") (pinfunction "P$2_P$2") (pintype "passive"))
      (node (ref "C9") (pin "P$2") (pinfunction "P$2_P$2") (pintype "passive"))
      (node (ref "CAN1") (pin "3") (pinfunction "3_3") (pintype "passive"))
      (node (ref "CAN2") (pin "3") (pinfunction "3_3") (pintype "passive"))
      (node (ref "DB_G") (pin "P$1") (pinfunction "P$1_P$1") (pintype "bidirectional"))
      (node (ref "J1") (pin "4") (pinfunction "4_4") (pintype "passive"))
      (node (ref "J2") (pin "2") (pinfunction "2_2") (pintype "passive"))
      (node (ref "J3") (pin "5") (pinfunction "5_5") (pintype "passive"))
      (node (ref "Q4") (pin "P$2") (pinfunction "EMITTER_P$2") (pintype "bidirectional"))
      (node (ref "Q5") (pin "P$3") (pinfunction "COLLECTOR_P$3") (pintype "bidirectional"))
      (node (ref "R1") (pin "P$2") (pinfunction "P$2_P$2") (pintype "passive"))
      (node (ref "R11") (pin "P$1") (pinfunction "P$1_P$1") (pintype "passive"))
      (node (ref "R13") (pin "P$1") (pinfunction "P$1_P$1") (pintype "passive"))
      (node (ref "R18") (pin "P$1") (pinfunction "P$1_P$1") (pintype "passive"))
      (node (ref "R2") (pin "P$1") (pinfunction "P$1_P$1") (pintype "passive"))
      (node (ref "SH4") (pin "1") (pinfunction "P$1_1") (pintype "bidirectional"))
      (node (ref "U1") (pin "7") (pinfunction "GND_7") (pintype "power_in"))
      (node (ref "U2") (pin "29") (pinfunction "PC6_29") (pintype "bidirectional"))
      (node (ref "U2") (pin "49") (pinfunction "THERMALPAD_49") (pintype "bidirectional"))
      (node (ref "U4") (pin "2") (pinfunction "GND_2") (pintype "power_in"))
      (node (ref "U4") (pin "8") (pinfunction "STB_8") (pintype "input"))
      (node (ref "U5") (pin "4") (pinfunction "VEE_4") (pintype "power_in"))
      (node (ref "U6") (pin "8") (pinfunction "GND_8") (pintype "bidirectional"))
      (node (ref "U6") (pin "P$1") (pinfunction "GND_P$1") (pintype "bidirectional"))
    )
    (net (code "35") (name "Net-(C13-PadP$1)") (class "Default")
      (node (ref "C13") (pin "P$1") (pinfunction "P$1_P$1") (pintype "passive"))
      (node (ref "R6") (pin "P$1") (pinfunction "P$1_P$1") (pintype "passive"))
    )
    (net (code "36") (name "Net-(D4-PadANODE)") (class "Default")
      (node (ref "D4") (pin "ANODE") (pinfunction "ANODE_ANODE") (pintype "power_in"))
      (node (ref "R8") (pin "P$1") (pinfunction "P$1_P$1") (pintype "passive"))
    )
    (net (code "37") (name "Net-(D5-PadANODE)") (class "Default")
      (node (ref "D5") (pin "ANODE") (pinfunction "ANODE_ANODE") (pintype "power_in"))
      (node (ref "R9") (pin "P$1") (pinfunction "P$1_P$1") (pintype "passive"))
    )
    (net (code "38") (name "Net-(D6-PadANODE)") (class "Default")
      (node (ref "D6") (pin "ANODE") (pinfunction "ANODE_ANODE") (pintype "bidirectional"))
      (node (ref "R16") (pin "P$1") (pinfunction "P$1_P$1") (pintype "passive"))
    )
    (net (code "39") (name "Net-(D7-PadANODE)") (class "Default")
      (node (ref "D7") (pin "ANODE") (pinfunction "ANODE_ANODE") (pintype "bidirectional"))
      (node (ref "R15") (pin "P$1") (pinfunction "P$1_P$1") (pintype "passive"))
    )
    (net (code "40") (name "Net-(J2-Pad1)") (class "Default")
      (node (ref "J2") (pin "1") (pinfunction "1_1") (pintype "passive"))
      (node (ref "R14") (pin "P$1") (pinfunction "P$1_P$1") (pintype "passive"))
    )
    (net (code "41") (name "Net-(Q4-BASE)") (class "Default")
      (node (ref "Q4") (pin "P$1") (pinfunction "BASE_P$1") (pintype "bidirectional"))
      (node (ref "R17") (pin "P$1") (pinfunction "P$1_P$1") (pintype "passive"))
    )
    (net (code "42") (name "Net-(Q5-BASE)") (class "Default")
      (node (ref "D6") (pin "CATHODE") (pinfunction "CATHODE_CATHODE") (pintype "bidirectional"))
      (node (ref "D7") (pin "CATHODE") (pinfunction "CATHODE_CATHODE") (pintype "bidirectional"))
      (node (ref "Q5") (pin "P$1") (pinfunction "BASE_P$1") (pintype "bidirectional"))
      (node (ref "R18") (pin "P$2") (pinfunction "P$2_P$2") (pintype "passive"))
    )
    (net (code "43") (name "Net-(U$3-1)") (class "Default")
      (node (ref "C1") (pin "P$1") (pinfunction "P$1_P$1") (pintype "passive"))
      (node (ref "R1") (pin "P$1") (pinfunction "P$1_P$1") (pintype "passive"))
      (node (ref "U$3") (pin "P$1") (pinfunction "1_P$1") (pintype "passive"))
    )
    (net (code "44") (name "Net-(U1-LX)") (class "Default")
      (node (ref "L1") (pin "2") (pinfunction "2_2") (pintype "passive"))
      (node (ref "U1") (pin "8") (pinfunction "LX_8") (pintype "passive"))
    )
    (net (code "45") (name "Net-(U1-VCC)") (class "Default")
      (node (ref "C3") (pin "P$1") (pinfunction "P$1_P$1") (pintype "passive"))
      (node (ref "U1") (pin "3") (pinfunction "VCC_3") (pintype "power_in"))
    )
    (net (code "46") (name "Net-(U5-FIL+)") (class "Default")
      (node (ref "C16") (pin "P$2") (pinfunction "P$2_P$2") (pintype "passive"))
      (node (ref "U5") (pin "8") (pinfunction "FIL+_8") (pintype "passive"))
    )
    (net (code "47") (name "Net-(U5-FIL-)") (class "Default")
      (node (ref "C16") (pin "P$1") (pinfunction "P$1_P$1") (pintype "passive"))
      (node (ref "U5") (pin "1") (pinfunction "FIL-_1") (pintype "passive"))
    )
    (net (code "48") (name "Net-(U6-DRN)") (class "Default")
      (node (ref "R4") (pin "P$1") (pinfunction "P$1_P$1") (pintype "passive"))
      (node (ref "U6") (pin "1") (pinfunction "DRN_1") (pintype "bidirectional"))
    )
    (net (code "49") (name "Net-(U6-GATE)") (class "Default")
      (node (ref "R5") (pin "P$1") (pinfunction "P$1_P$1") (pintype "passive"))
      (node (ref "R6") (pin "P$2") (pinfunction "P$2_P$2") (pintype "passive"))
      (node (ref "U6") (pin "3") (pinfunction "GATE_3") (pintype "bidirectional"))
    )
    (net (code "50") (name "Net-(U6-TMR)") (class "Default")
      (node (ref "C14") (pin "P$1") (pinfunction "P$1_P$1") (pintype "passive"))
      (node (ref "U6") (pin "10") (pinfunction "TMR_10") (pintype "bidirectional"))
    )
    (net (code "51") (name "VCC") (class "Default")
      (node (ref "C10") (pin "P$1") (pinfunction "P$1_P$1") (pintype "passive"))
      (node (ref "C11") (pin "P$1") (pinfunction "P$1_P$1") (pintype "passive"))
      (node (ref "C20") (pin "P$1") (pinfunction "P$1_P$1") (pintype "passive"))
      (node (ref "C4") (pin "P$1") (pinfunction "P$1_P$1") (pintype "passive"))
      (node (ref "C6") (pin "P$1") (pinfunction "P$1_P$1") (pintype "passive"))
      (node (ref "C7") (pin "P$1") (pinfunction "P$1_P$1") (pintype "passive"))
      (node (ref "C8") (pin "P$1") (pinfunction "P$1_P$1") (pintype "passive"))
      (node (ref "C9") (pin "P$1") (pinfunction "P$1_P$1") (pintype "passive"))
      (node (ref "DB_3") (pin "P$1") (pinfunction "P$1_P$1") (pintype "bidirectional"))
      (node (ref "J1") (pin "6") (pinfunction "6_6") (pintype "passive"))
      (node (ref "J3") (pin "1") (pinfunction "1_1") (pintype "passive"))
      (node (ref "L1") (pin "1") (pinfunction "1_1") (pintype "passive"))
      (node (ref "R8") (pin "P$2") (pinfunction "P$2_P$2") (pintype "passive"))
      (node (ref "R9") (pin "P$2") (pinfunction "P$2_P$2") (pintype "passive"))
      (node (ref "U1") (pin "4") (pinfunction "FB/VOUT_4") (pintype "bidirectional"))
      (node (ref "U2") (pin "1") (pinfunction "VBAT_1") (pintype "bidirectional"))
      (node (ref "U2") (pin "20") (pinfunction "VREF+_20") (pintype "bidirectional"))
      (node (ref "U2") (pin "21") (pinfunction "VDDA_21") (pintype "bidirectional"))
      (node (ref "U2") (pin "23") (pinfunction "VDD_1_23") (pintype "bidirectional"))
      (node (ref "U2") (pin "35") (pinfunction "VDD_2_35") (pintype "bidirectional"))
      (node (ref "U2") (pin "48") (pinfunction "VDD_3_48") (pintype "bidirectional"))
      (node (ref "U4") (pin "3") (pinfunction "VCC_3") (pintype "power_in"))
    )
    (net (code "52") (name "unconnected-(J1-Pad1)") (class "Default")
      (node (ref "J1") (pin "1") (pinfunction "1_1") (pintype "passive"))
    )
    (net (code "53") (name "unconnected-(U$1-1-PadP$1)") (class "Default")
      (node (ref "U$1") (pin "P$1") (pinfunction "1_P$1") (pintype "passive"))
    )
    (net (code "54") (name "unconnected-(U$2-1-PadP$1)") (class "Default")
      (node (ref "U$2") (pin "P$1") (pinfunction "1_P$1") (pintype "passive"))
    )
    (net (code "55") (name "unconnected-(U$4-1-PadP$1)") (class "Default")
      (node (ref "U$4") (pin "P$1") (pinfunction "1_P$1") (pintype "passive"))
    )
    (net (code "56") (name "unconnected-(U1-MODE-Pad5)") (class "Default")
      (node (ref "U1") (pin "5") (pinfunction "MODE_5") (pintype "input"))
    )
    (net (code "57") (name "unconnected-(U1-~{RESET}-Pad6)") (class "Default")
      (node (ref "U1") (pin "6") (pinfunction "~{RESET}_6") (pintype "output"))
    )
    (net (code "58") (name "unconnected-(U2-PA6-Pad14)") (class "Default")
      (node (ref "U2") (pin "14") (pinfunction "PA6_14") (pintype "bidirectional"))
    )
    (net (code "59") (name "unconnected-(U2-PA8-Pad30)") (class "Default")
      (node (ref "U2") (pin "30") (pinfunction "PA8_30") (pintype "bidirectional"))
    )
    (net (code "60") (name "unconnected-(U2-PA9-Pad31)") (class "Default")
      (node (ref "U2") (pin "31") (pinfunction "PA9_31") (pintype "bidirectional"))
    )
    (net (code "61") (name "unconnected-(U2-PA10-Pad32)") (class "Default")
      (node (ref "U2") (pin "32") (pinfunction "PA10_32") (pintype "bidirectional"))
    )
    (net (code "62") (name "unconnected-(U2-PB0-Pad17)") (class "Default")
      (node (ref "U2") (pin "17") (pinfunction "PB0_17") (pintype "bidirectional"))
    )
    (net (code "63") (name "unconnected-(U2-PB1-Pad18)") (class "Default")
      (node (ref "U2") (pin "18") (pinfunction "PB1_18") (pintype "bidirectional"))
    )
    (net (code "64") (name "unconnected-(U2-PB2-Pad19)") (class "Default")
      (node (ref "U2") (pin "19") (pinfunction "PB2_19") (pintype "bidirectional"))
    )
    (net (code "65") (name "unconnected-(U2-PB4-Pad42)") (class "Default")
      (node (ref "U2") (pin "42") (pinfunction "PB4_42") (pintype "bidirectional"))
    )
    (net (code "66") (name "unconnected-(U2-PB5-Pad43)") (class "Default")
      (node (ref "U2") (pin "43") (pinfunction "PB5_43") (pintype "bidirectional"))
    )
    (net (code "67") (name "unconnected-(U2-PB6-Pad44)") (class "Default")
      (node (ref "U2") (pin "44") (pinfunction "PB6_44") (pintype "bidirectional"))
    )
    (net (code "68") (name "unconnected-(U2-PB7-Pad45)") (class "Default")
      (node (ref "U2") (pin "45") (pinfunction "PB7_45") (pintype "bidirectional"))
    )
    (net (code "69") (name "unconnected-(U2-PB8-BOOT0-Pad46)") (class "Default")
      (node (ref "U2") (pin "46") (pinfunction "PB8-BOOT0_46") (pintype "bidirectional"))
    )
    (net (code "70") (name "unconnected-(U2-PB9-Pad47)") (class "Default")
      (node (ref "U2") (pin "47") (pinfunction "PB9_47") (pintype "bidirectional"))
    )
    (net (code "71") (name "unconnected-(U2-PB11-Pad24)") (class "Default")
      (node (ref "U2") (pin "24") (pinfunction "PB11_24") (pintype "bidirectional"))
    )
    (net (code "72") (name "unconnected-(U2-PB15-Pad28)") (class "Default")
      (node (ref "U2") (pin "28") (pinfunction "PB15_28") (pintype "bidirectional"))
    )
    (net (code "73") (name "unconnected-(U2-PC4-Pad16)") (class "Default")
      (node (ref "U2") (pin "16") (pinfunction "PC4_16") (pintype "bidirectional"))
    )
    (net (code "74") (name "unconnected-(U2-PC13-Pad2)") (class "Default")
      (node (ref "U2") (pin "2") (pinfunction "PC13_2") (pintype "bidirectional"))
    )
    (net (code "75") (name "unconnected-(U2-PC14-OSC32_IN-Pad3)") (class "Default")
      (node (ref "U2") (pin "3") (pinfunction "PC14-OSC32_IN_3") (pintype "bidirectional"))
    )
    (net (code "76") (name "unconnected-(U2-PC15-OSC32_OUT-Pad4)") (class "Default")
      (node (ref "U2") (pin "4") (pinfunction "PC15-OSC32_OUT_4") (pintype "bidirectional"))
    )
    (net (code "77") (name "unconnected-(U2-PF0-OSC_IN-Pad5)") (class "Default")
      (node (ref "U2") (pin "5") (pinfunction "PF0-OSC_IN_5") (pintype "bidirectional"))
    )
    (net (code "78") (name "unconnected-(U2-PF1-OSC_OUT-Pad6)") (class "Default")
      (node (ref "U2") (pin "6") (pinfunction "PF1-OSC_OUT_6") (pintype "bidirectional"))
    )
    (net (code "79") (name "unconnected-(U5-DNC-Pad3)") (class "Default")
      (node (ref "U5") (pin "3") (pinfunction "DNC_3") (pintype "no_connect"))
    )
  )
)
